# Sheet1.net
KiCad netlist of a schematic drawn in Altium Designer
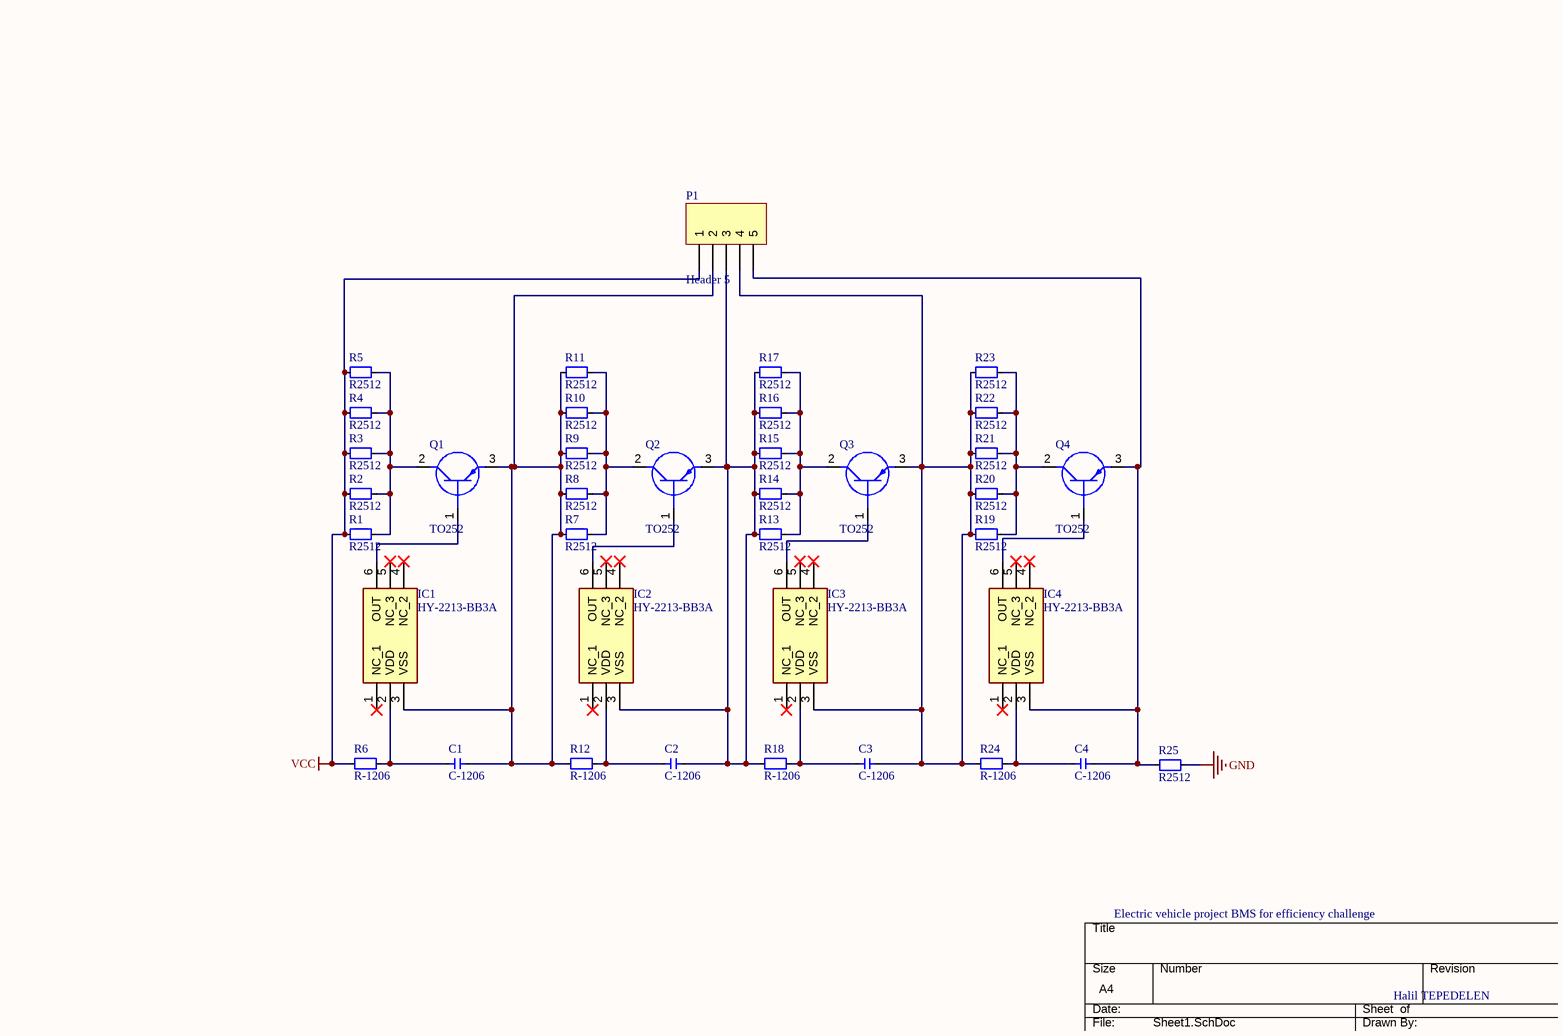
[diagram p0: Sheet1.SchDoc]

(export (version "E")
  (design (tool "Eeschema 10.0.6"))
  (components
    (comp (ref "C1") (value "C-1206") (footprint "PcbLib1:C1206") (libsource (lib "Schlib1") (part "C-1206")))
    (comp (ref "C2") (value "C-1206") (footprint "PcbLib1:C1206") (libsource (lib "Schlib1") (part "C-1206")))
    (comp (ref "C3") (value "C-1206") (footprint "PcbLib1:C1206") (libsource (lib "Schlib1") (part "C-1206")))
    (comp (ref "C4") (value "C-1206") (footprint "PcbLib1:C1206") (libsource (lib "Schlib1") (part "C-1206")))
    (comp (ref "IC1")
      (value "HY-2213-BB3A")
      (footprint "PcbLib1:HY223")
      (libsource (lib "Schlib1") (part "HY-2213-BB3A"))
    )
    (comp (ref "IC2")
      (value "HY-2213-BB3A")
      (footprint "PcbLib1:HY223")
      (libsource (lib "Schlib1") (part "HY-2213-BB3A"))
    )
    (comp (ref "IC3")
      (value "HY-2213-BB3A")
      (footprint "PcbLib1:HY223")
      (libsource (lib "Schlib1") (part "HY-2213-BB3A"))
    )
    (comp (ref "IC4")
      (value "HY-2213-BB3A")
      (footprint "PcbLib1:HY223")
      (libsource (lib "Schlib1") (part "HY-2213-BB3A"))
    )
    (comp (ref "P1")
      (value "Header 5")
      (footprint "HDR1X5")
      (description "Header, 5-Pin")
      (fields (field (name "PUBLISHER") "Altium Limited"))
      (libsource (lib "Miscellaneous Connectors") (part "Header 5"))
    )
    (comp (ref "Q1") (value "TO252") (footprint "PcbLib1:TO252") (libsource (lib "Schlib1") (part "TO252")))
    (comp (ref "Q2") (value "TO252") (footprint "PcbLib1:TO252") (libsource (lib "Schlib1") (part "TO252")))
    (comp (ref "Q3") (value "TO252") (footprint "PcbLib1:TO252") (libsource (lib "Schlib1") (part "TO252")))
    (comp (ref "Q4") (value "TO252") (footprint "PcbLib1:TO252") (libsource (lib "Schlib1") (part "TO252")))
    (comp (ref "R1") (value "R2512") (footprint "PcbLib1:R2512") (libsource (lib "Schlib1") (part "R2512")))
    (comp (ref "R2") (value "R2512") (footprint "PcbLib1:R2512") (libsource (lib "Schlib1") (part "R2512")))
    (comp (ref "R3") (value "R2512") (footprint "PcbLib1:R2512") (libsource (lib "Schlib1") (part "R2512")))
    (comp (ref "R4") (value "R2512") (footprint "PcbLib1:R2512") (libsource (lib "Schlib1") (part "R2512")))
    (comp (ref "R5") (value "R2512") (footprint "PcbLib1:R2512") (libsource (lib "Schlib1") (part "R2512")))
    (comp (ref "R6") (value "R-1206") (footprint "PcbLib1:R1206") (libsource (lib "Schlib1") (part "R-1206")))
    (comp (ref "R7") (value "R2512") (footprint "PcbLib1:R2512") (libsource (lib "Schlib1") (part "R2512")))
    (comp (ref "R8") (value "R2512") (footprint "PcbLib1:R2512") (libsource (lib "Schlib1") (part "R2512")))
    (comp (ref "R9") (value "R2512") (footprint "PcbLib1:R2512") (libsource (lib "Schlib1") (part "R2512")))
    (comp (ref "R10") (value "R2512") (footprint "PcbLib1:R2512") (libsource (lib "Schlib1") (part "R2512")))
    (comp (ref "R11") (value "R2512") (footprint "PcbLib1:R2512") (libsource (lib "Schlib1") (part "R2512")))
    (comp (ref "R12")
      (value "R-1206")
      (footprint "PcbLib1:R1206")
      (libsource (lib "Schlib1") (part "R-1206"))
    )
    (comp (ref "R13") (value "R2512") (footprint "PcbLib1:R2512") (libsource (lib "Schlib1") (part "R2512")))
    (comp (ref "R14") (value "R2512") (footprint "PcbLib1:R2512") (libsource (lib "Schlib1") (part "R2512")))
    (comp (ref "R15") (value "R2512") (footprint "PcbLib1:R2512") (libsource (lib "Schlib1") (part "R2512")))
    (comp (ref "R16") (value "R2512") (footprint "PcbLib1:R2512") (libsource (lib "Schlib1") (part "R2512")))
    (comp (ref "R17") (value "R2512") (footprint "PcbLib1:R2512") (libsource (lib "Schlib1") (part "R2512")))
    (comp (ref "R18")
      (value "R-1206")
      (footprint "PcbLib1:R1206")
      (libsource (lib "Schlib1") (part "R-1206"))
    )
    (comp (ref "R19") (value "R2512") (footprint "PcbLib1:R2512") (libsource (lib "Schlib1") (part "R2512")))
    (comp (ref "R20") (value "R2512") (footprint "PcbLib1:R2512") (libsource (lib "Schlib1") (part "R2512")))
    (comp (ref "R21") (value "R2512") (footprint "PcbLib1:R2512") (libsource (lib "Schlib1") (part "R2512")))
    (comp (ref "R22") (value "R2512") (footprint "PcbLib1:R2512") (libsource (lib "Schlib1") (part "R2512")))
    (comp (ref "R23") (value "R2512") (footprint "PcbLib1:R2512") (libsource (lib "Schlib1") (part "R2512")))
    (comp (ref "R24")
      (value "R-1206")
      (footprint "PcbLib1:R1206")
      (libsource (lib "Schlib1") (part "R-1206"))
    )
    (comp (ref "R25") (value "R2512") (footprint "PcbLib1:R2512") (libsource (lib "Schlib1") (part "R2512")))
  )
  (nets
    (net (code "1") (name "GND") (class "Default")
      (node (ref "R25") (pin "1") (pinfunction "1_1") (pintype "passive"))
    )
    (net (code "2") (name "Net-(IC1-OUT)") (class "Default")
      (node (ref "IC1") (pin "6") (pinfunction "OUT_6") (pintype "passive"))
      (node (ref "Q1") (pin "1") (pinfunction "B_1") (pintype "passive"))
    )
    (net (code "3") (name "Net-(IC1-VDD)") (class "Default")
      (node (ref "C1") (pin "2") (pinfunction "2_2") (pintype "passive"))
      (node (ref "IC1") (pin "2") (pinfunction "VDD_2") (pintype "passive"))
      (node (ref "R6") (pin "1") (pinfunction "1_1") (pintype "passive"))
    )
    (net (code "4") (name "Net-(IC1-VSS)") (class "Default")
      (node (ref "C1") (pin "1") (pinfunction "1_1") (pintype "passive"))
      (node (ref "IC1") (pin "3") (pinfunction "VSS_3") (pintype "passive"))
      (node (ref "P1") (pin "2") (pinfunction "2_2") (pintype "passive"))
      (node (ref "Q1") (pin "3") (pinfunction "E_3") (pintype "passive"))
      (node (ref "R10") (pin "2") (pinfunction "2_2") (pintype "passive"))
      (node (ref "R11") (pin "2") (pinfunction "2_2") (pintype "passive"))
      (node (ref "R12") (pin "2") (pinfunction "2_2") (pintype "passive"))
      (node (ref "R7") (pin "2") (pinfunction "2_2") (pintype "passive"))
      (node (ref "R8") (pin "2") (pinfunction "2_2") (pintype "passive"))
      (node (ref "R9") (pin "2") (pinfunction "2_2") (pintype "passive"))
    )
    (net (code "5") (name "Net-(IC2-OUT)") (class "Default")
      (node (ref "IC2") (pin "6") (pinfunction "OUT_6") (pintype "passive"))
      (node (ref "Q2") (pin "1") (pinfunction "B_1") (pintype "passive"))
    )
    (net (code "6") (name "Net-(IC2-VDD)") (class "Default")
      (node (ref "C2") (pin "2") (pinfunction "2_2") (pintype "passive"))
      (node (ref "IC2") (pin "2") (pinfunction "VDD_2") (pintype "passive"))
      (node (ref "R12") (pin "1") (pinfunction "1_1") (pintype "passive"))
    )
    (net (code "7") (name "Net-(IC2-VSS)") (class "Default")
      (node (ref "C2") (pin "1") (pinfunction "1_1") (pintype "passive"))
      (node (ref "IC2") (pin "3") (pinfunction "VSS_3") (pintype "passive"))
      (node (ref "P1") (pin "3") (pinfunction "3_3") (pintype "passive"))
      (node (ref "Q2") (pin "3") (pinfunction "E_3") (pintype "passive"))
      (node (ref "R13") (pin "2") (pinfunction "2_2") (pintype "passive"))
      (node (ref "R14") (pin "2") (pinfunction "2_2") (pintype "passive"))
      (node (ref "R15") (pin "2") (pinfunction "2_2") (pintype "passive"))
      (node (ref "R16") (pin "2") (pinfunction "2_2") (pintype "passive"))
      (node (ref "R17") (pin "2") (pinfunction "2_2") (pintype "passive"))
      (node (ref "R18") (pin "2") (pinfunction "2_2") (pintype "passive"))
    )
    (net (code "8") (name "Net-(IC3-OUT)") (class "Default")
      (node (ref "IC3") (pin "6") (pinfunction "OUT_6") (pintype "passive"))
      (node (ref "Q3") (pin "1") (pinfunction "B_1") (pintype "passive"))
    )
    (net (code "9") (name "Net-(IC3-VDD)") (class "Default")
      (node (ref "C3") (pin "2") (pinfunction "2_2") (pintype "passive"))
      (node (ref "IC3") (pin "2") (pinfunction "VDD_2") (pintype "passive"))
      (node (ref "R18") (pin "1") (pinfunction "1_1") (pintype "passive"))
    )
    (net (code "10") (name "Net-(IC3-VSS)") (class "Default")
      (node (ref "C3") (pin "1") (pinfunction "1_1") (pintype "passive"))
      (node (ref "IC3") (pin "3") (pinfunction "VSS_3") (pintype "passive"))
      (node (ref "P1") (pin "4") (pinfunction "4_4") (pintype "passive"))
      (node (ref "Q3") (pin "3") (pinfunction "E_3") (pintype "passive"))
      (node (ref "R19") (pin "2") (pinfunction "2_2") (pintype "passive"))
      (node (ref "R20") (pin "2") (pinfunction "2_2") (pintype "passive"))
      (node (ref "R21") (pin "2") (pinfunction "2_2") (pintype "passive"))
      (node (ref "R22") (pin "2") (pinfunction "2_2") (pintype "passive"))
      (node (ref "R23") (pin "2") (pinfunction "2_2") (pintype "passive"))
      (node (ref "R24") (pin "2") (pinfunction "2_2") (pintype "passive"))
    )
    (net (code "11") (name "Net-(IC4-OUT)") (class "Default")
      (node (ref "IC4") (pin "6") (pinfunction "OUT_6") (pintype "passive"))
      (node (ref "Q4") (pin "1") (pinfunction "B_1") (pintype "passive"))
    )
    (net (code "12") (name "Net-(IC4-VDD)") (class "Default")
      (node (ref "C4") (pin "2") (pinfunction "2_2") (pintype "passive"))
      (node (ref "IC4") (pin "2") (pinfunction "VDD_2") (pintype "passive"))
      (node (ref "R24") (pin "1") (pinfunction "1_1") (pintype "passive"))
    )
    (net (code "13") (name "Net-(IC4-VSS)") (class "Default")
      (node (ref "C4") (pin "1") (pinfunction "1_1") (pintype "passive"))
      (node (ref "IC4") (pin "3") (pinfunction "VSS_3") (pintype "passive"))
      (node (ref "P1") (pin "5") (pinfunction "5_5") (pintype "passive"))
      (node (ref "Q4") (pin "3") (pinfunction "E_3") (pintype "passive"))
      (node (ref "R25") (pin "2") (pinfunction "2_2") (pintype "passive"))
    )
    (net (code "14") (name "Net-(Q1-C)") (class "Default")
      (node (ref "Q1") (pin "2") (pinfunction "C_2") (pintype "passive"))
      (node (ref "R1") (pin "1") (pinfunction "1_1") (pintype "passive"))
      (node (ref "R2") (pin "1") (pinfunction "1_1") (pintype "passive"))
      (node (ref "R3") (pin "1") (pinfunction "1_1") (pintype "passive"))
      (node (ref "R4") (pin "1") (pinfunction "1_1") (pintype "passive"))
      (node (ref "R5") (pin "1") (pinfunction "1_1") (pintype "passive"))
    )
    (net (code "15") (name "Net-(Q2-C)") (class "Default")
      (node (ref "Q2") (pin "2") (pinfunction "C_2") (pintype "passive"))
      (node (ref "R10") (pin "1") (pinfunction "1_1") (pintype "passive"))
      (node (ref "R11") (pin "1") (pinfunction "1_1") (pintype "passive"))
      (node (ref "R7") (pin "1") (pinfunction "1_1") (pintype "passive"))
      (node (ref "R8") (pin "1") (pinfunction "1_1") (pintype "passive"))
      (node (ref "R9") (pin "1") (pinfunction "1_1") (pintype "passive"))
    )
    (net (code "16") (name "Net-(Q3-C)") (class "Default")
      (node (ref "Q3") (pin "2") (pinfunction "C_2") (pintype "passive"))
      (node (ref "R13") (pin "1") (pinfunction "1_1") (pintype "passive"))
      (node (ref "R14") (pin "1") (pinfunction "1_1") (pintype "passive"))
      (node (ref "R15") (pin "1") (pinfunction "1_1") (pintype "passive"))
      (node (ref "R16") (pin "1") (pinfunction "1_1") (pintype "passive"))
      (node (ref "R17") (pin "1") (pinfunction "1_1") (pintype "passive"))
    )
    (net (code "17") (name "Net-(Q4-C)") (class "Default")
      (node (ref "Q4") (pin "2") (pinfunction "C_2") (pintype "passive"))
      (node (ref "R19") (pin "1") (pinfunction "1_1") (pintype "passive"))
      (node (ref "R20") (pin "1") (pinfunction "1_1") (pintype "passive"))
      (node (ref "R21") (pin "1") (pinfunction "1_1") (pintype "passive"))
      (node (ref "R22") (pin "1") (pinfunction "1_1") (pintype "passive"))
      (node (ref "R23") (pin "1") (pinfunction "1_1") (pintype "passive"))
    )
    (net (code "18") (name "VCC") (class "Default")
      (node (ref "P1") (pin "1") (pinfunction "1_1") (pintype "passive"))
      (node (ref "R1") (pin "2") (pinfunction "2_2") (pintype "passive"))
      (node (ref "R2") (pin "2") (pinfunction "2_2") (pintype "passive"))
      (node (ref "R3") (pin "2") (pinfunction "2_2") (pintype "passive"))
      (node (ref "R4") (pin "2") (pinfunction "2_2") (pintype "passive"))
      (node (ref "R5") (pin "2") (pinfunction "2_2") (pintype "passive"))
      (node (ref "R6") (pin "2") (pinfunction "2_2") (pintype "passive"))
    )
    (net (code "19") (name "unconnected-(IC1-NC_1-Pad1)") (class "Default")
      (node (ref "IC1") (pin "1") (pinfunction "NC_1_1") (pintype "passive+no_connect"))
    )
    (net (code "20") (name "unconnected-(IC1-NC_2-Pad4)") (class "Default")
      (node (ref "IC1") (pin "4") (pinfunction "NC_2_4") (pintype "passive+no_connect"))
    )
    (net (code "21") (name "unconnected-(IC1-NC_3-Pad5)") (class "Default")
      (node (ref "IC1") (pin "5") (pinfunction "NC_3_5") (pintype "passive+no_connect"))
    )
    (net (code "22") (name "unconnected-(IC2-NC_1-Pad1)") (class "Default")
      (node (ref "IC2") (pin "1") (pinfunction "NC_1_1") (pintype "passive+no_connect"))
    )
    (net (code "23") (name "unconnected-(IC2-NC_2-Pad4)") (class "Default")
      (node (ref "IC2") (pin "4") (pinfunction "NC_2_4") (pintype "passive+no_connect"))
    )
    (net (code "24") (name "unconnected-(IC2-NC_3-Pad5)") (class "Default")
      (node (ref "IC2") (pin "5") (pinfunction "NC_3_5") (pintype "passive+no_connect"))
    )
    (net (code "25") (name "unconnected-(IC3-NC_1-Pad1)") (class "Default")
      (node (ref "IC3") (pin "1") (pinfunction "NC_1_1") (pintype "passive+no_connect"))
    )
    (net (code "26") (name "unconnected-(IC3-NC_2-Pad4)") (class "Default")
      (node (ref "IC3") (pin "4") (pinfunction "NC_2_4") (pintype "passive+no_connect"))
    )
    (net (code "27") (name "unconnected-(IC3-NC_3-Pad5)") (class "Default")
      (node (ref "IC3") (pin "5") (pinfunction "NC_3_5") (pintype "passive+no_connect"))
    )
    (net (code "28") (name "unconnected-(IC4-NC_1-Pad1)") (class "Default")
      (node (ref "IC4") (pin "1") (pinfunction "NC_1_1") (pintype "passive+no_connect"))
    )
    (net (code "29") (name "unconnected-(IC4-NC_2-Pad4)") (class "Default")
      (node (ref "IC4") (pin "4") (pinfunction "NC_2_4") (pintype "passive+no_connect"))
    )
    (net (code "30") (name "unconnected-(IC4-NC_3-Pad5)") (class "Default")
      (node (ref "IC4") (pin "5") (pinfunction "NC_3_5") (pintype "passive+no_connect"))
    )
  )
)
